# atx4vc.net
KiCad netlist of a schematic drawn in EAGLE
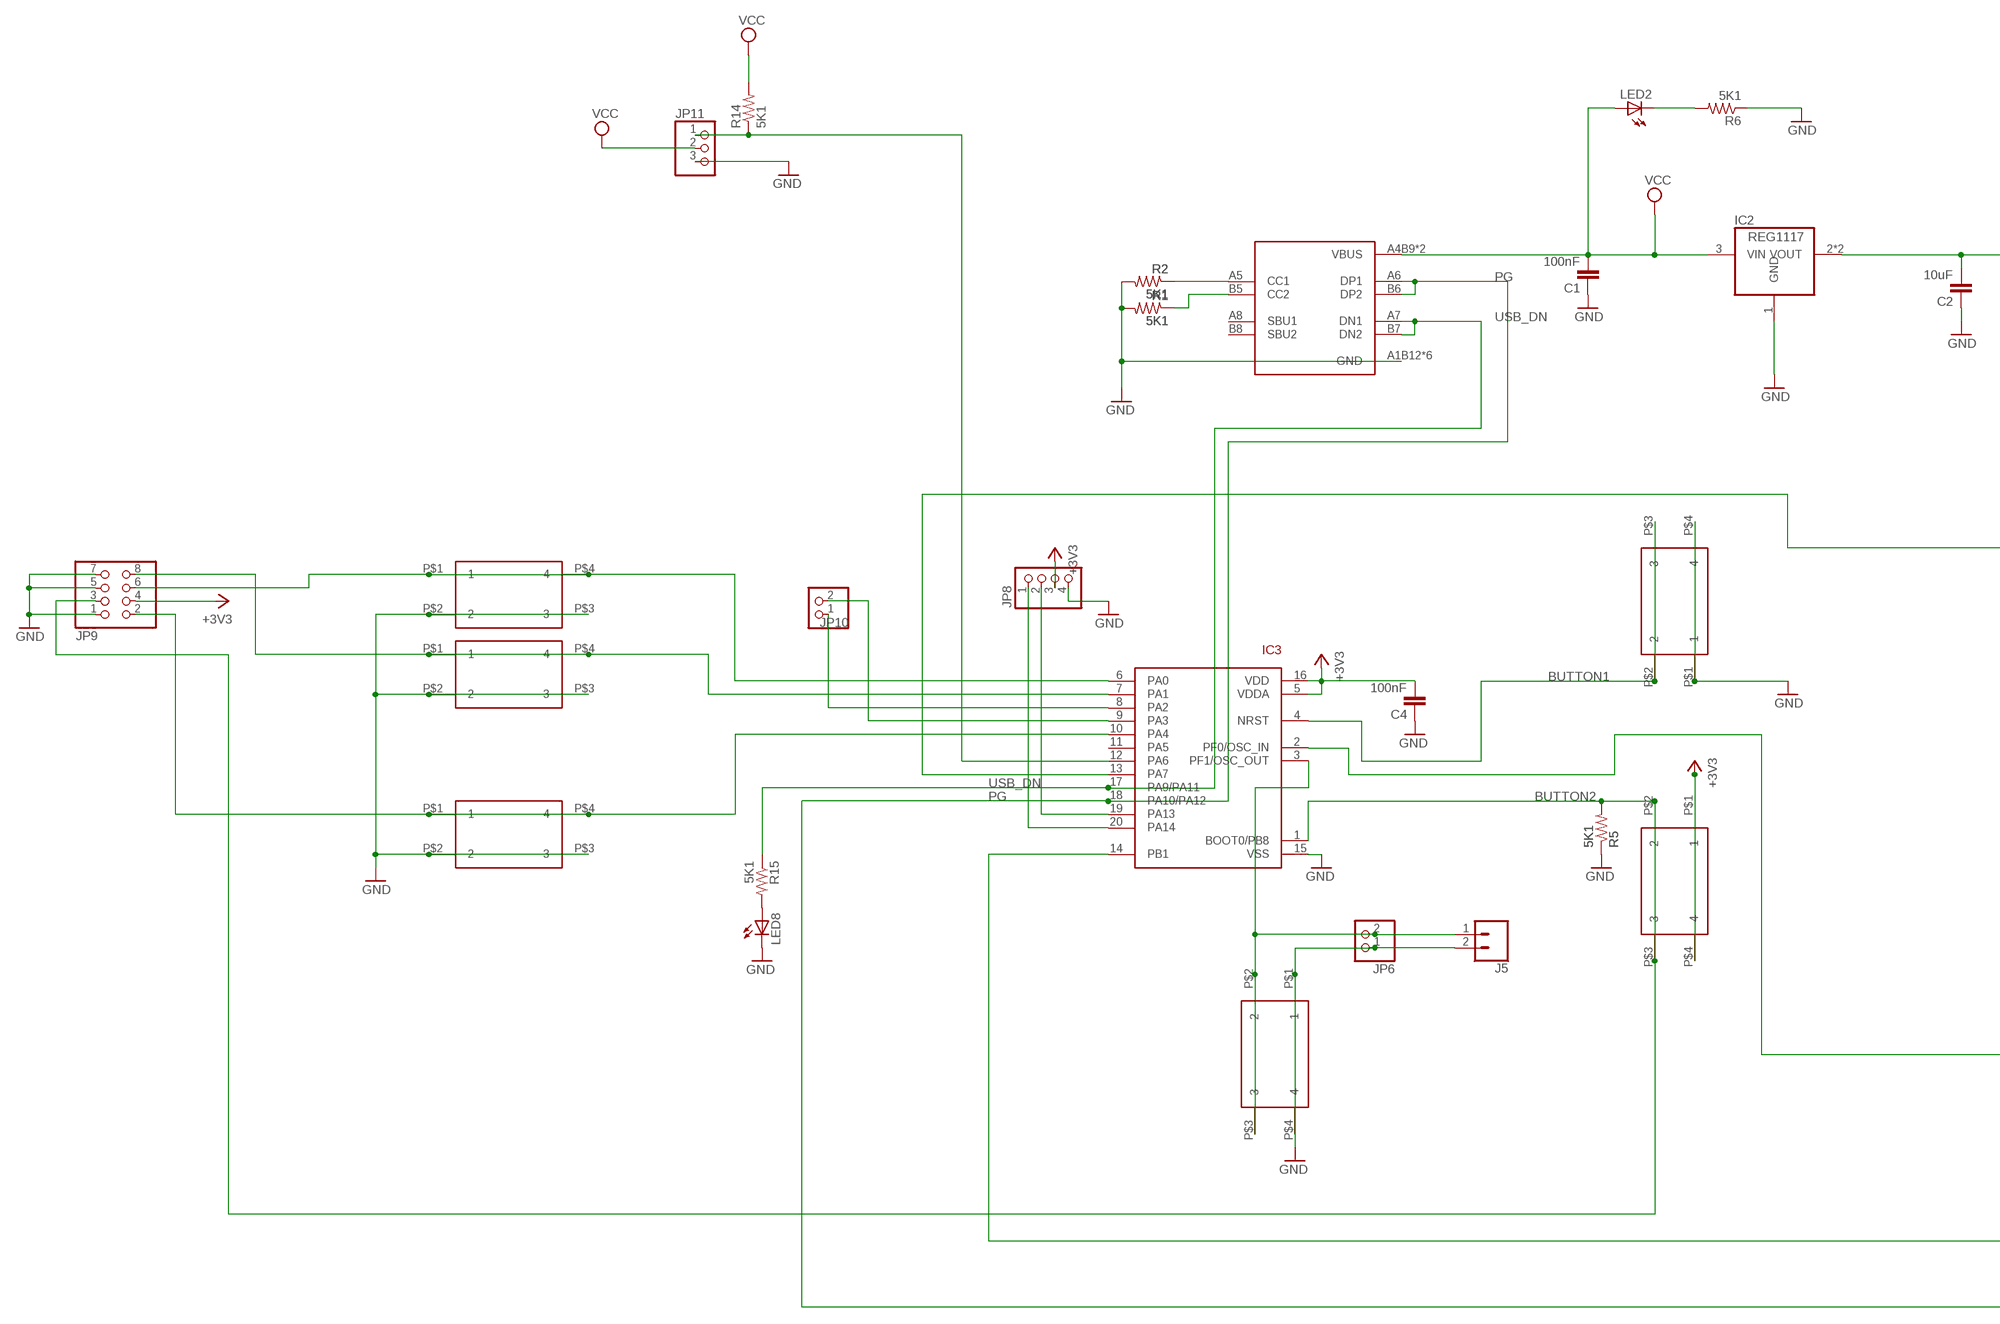
[diagram p0: schematic, sheet 1, part 1 of 2]
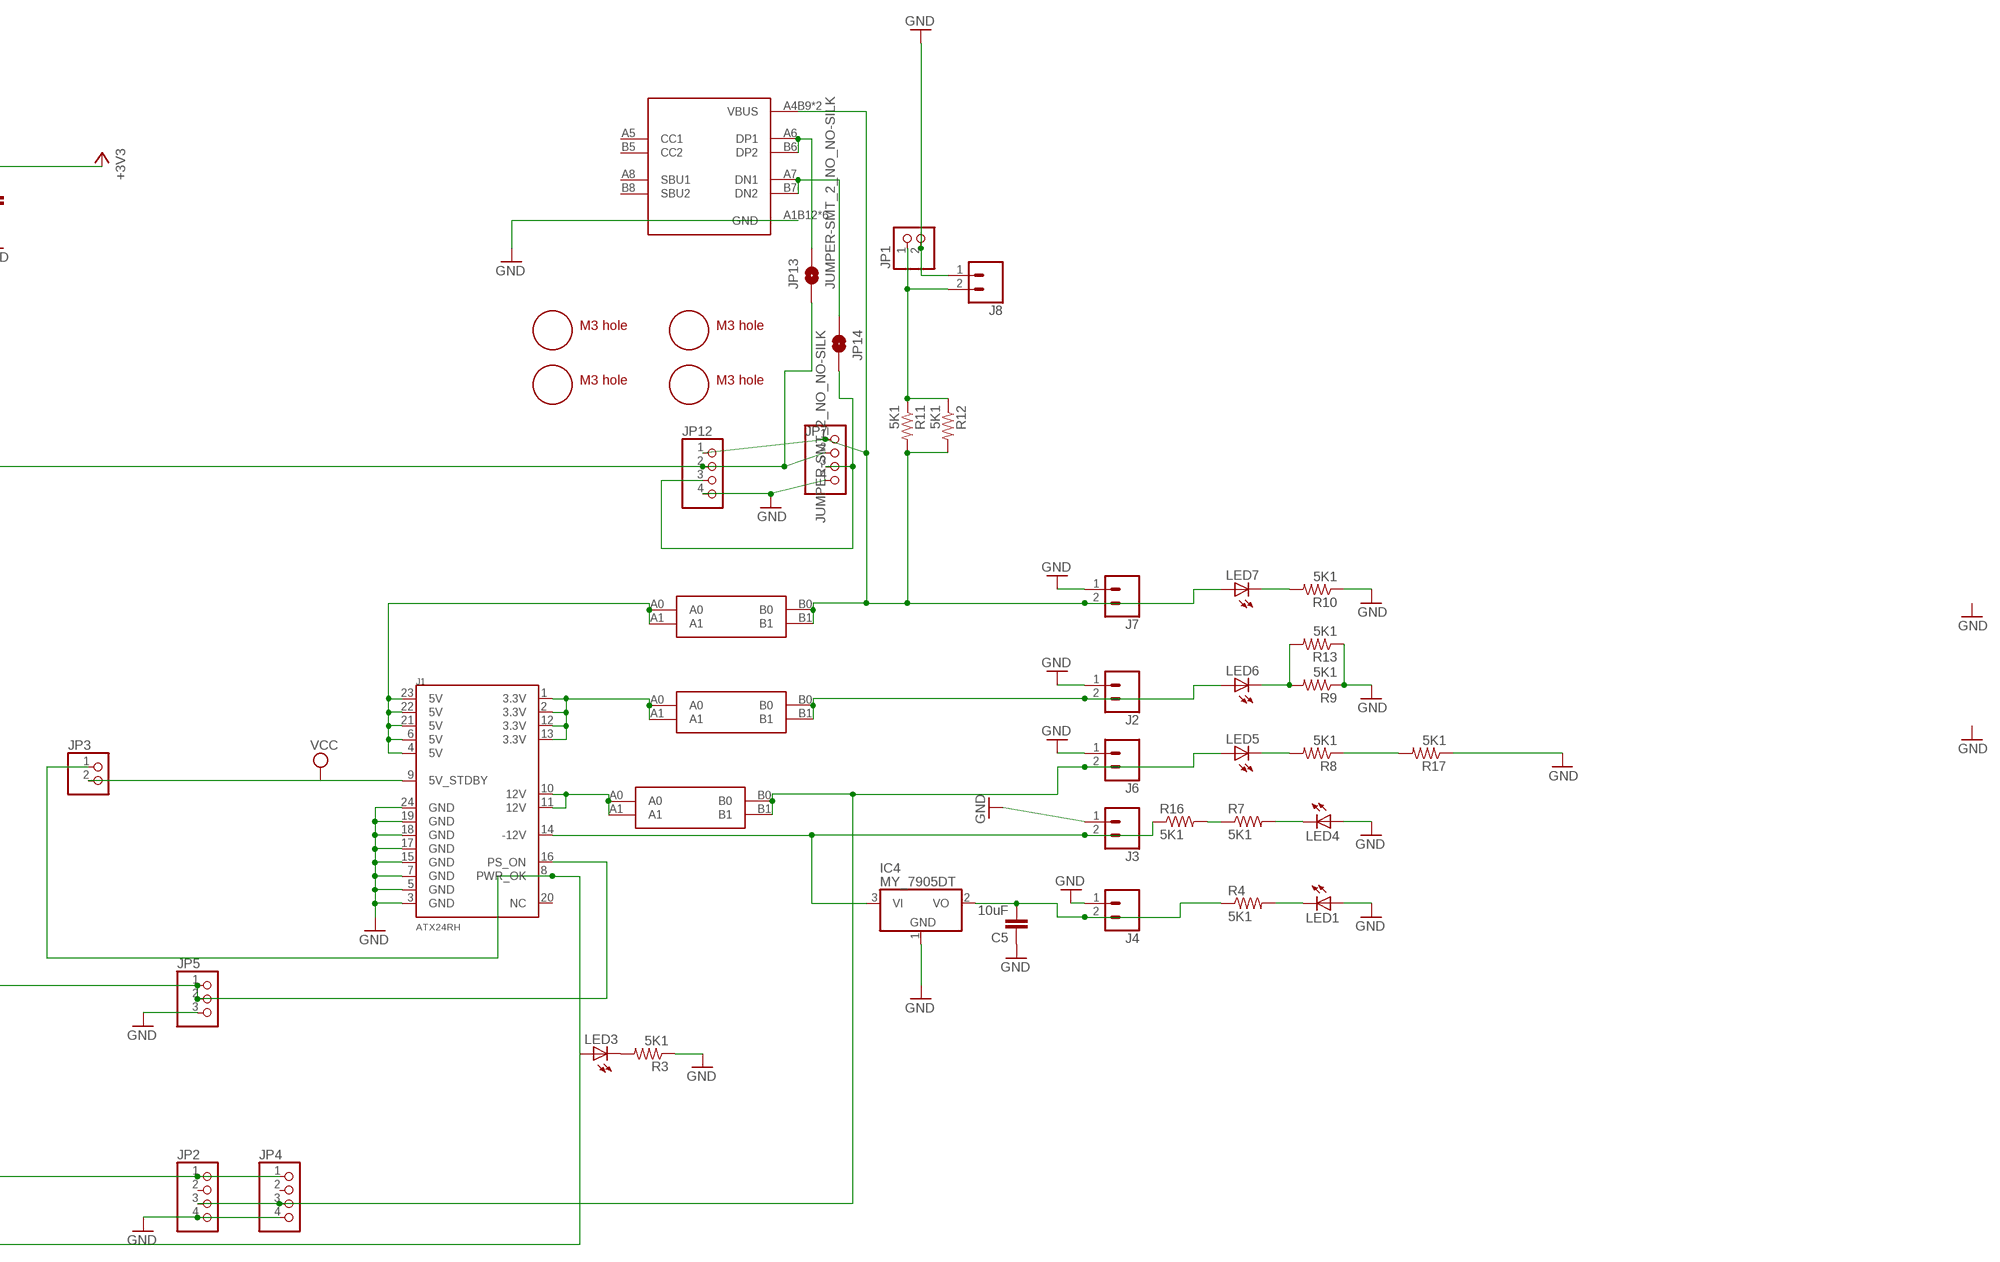
[diagram p1: schematic, sheet 1, part 2 of 2]

(export (version "E")
  (design (tool "Eeschema 10.0.6"))
  (components
    (comp (ref "C1")
      (value "100nF")
      (footprint "eagle-import:0805$1")
      (libsource (lib "eagle-import") (part "CAP0805"))
    )
    (comp (ref "C2")
      (value "10uF")
      (footprint "eagle-import:0805$1")
      (libsource (lib "eagle-import") (part "CAP0805"))
    )
    (comp (ref "C4")
      (value "100nF")
      (footprint "eagle-import:0805$1")
      (libsource (lib "eagle-import") (part "CAP0805"))
    )
    (comp (ref "C5")
      (value "10uF")
      (footprint "eagle-import:0805$1")
      (libsource (lib "eagle-import") (part "CAP0805"))
    )
    (comp (ref "IC2")
      (value "REG1117")
      (footprint "eagle-import:SOT223")
      (fields (field (name "MF") "TEXAS INSTRUMENTS") (field (name "MPN") "REG1117FAKTTT"))
      (libsource (lib "eagle-import") (part "REG1117"))
    )
    (comp (ref "IC3")
      (value "STM32F042F4")
      (footprint "eagle-import:TSSOP20")
      (libsource (lib "eagle-import") (part "STM32F042F4"))
    )
    (comp (ref "IC4")
      (value "MY_7905DT")
      (footprint "eagle-import:ADAFRUIT_TO252")
      (libsource (lib "eagle-import") (part "MY_7905DT"))
    )
    (comp (ref "J1")
      (value "ATX24RH")
      (footprint "eagle-import:ATX24_RIGHT_ANGLE")
      (libsource (lib "eagle-import") (part "ATX24RH"))
    )
    (comp (ref "J2")
      (value "CONN_023.5MM")
      (footprint "eagle-import:SCREWTERMINAL-3.5MM-2")
      (libsource (lib "eagle-import") (part "CONN_023.5MM"))
    )
    (comp (ref "J3")
      (value "CONN_023.5MM")
      (footprint "eagle-import:SCREWTERMINAL-3.5MM-2")
      (libsource (lib "eagle-import") (part "CONN_023.5MM"))
    )
    (comp (ref "J4")
      (value "CONN_023.5MM")
      (footprint "eagle-import:SCREWTERMINAL-3.5MM-2")
      (libsource (lib "eagle-import") (part "CONN_023.5MM"))
    )
    (comp (ref "J5")
      (value "CONN_023.5MM")
      (footprint "eagle-import:SCREWTERMINAL-3.5MM-2")
      (libsource (lib "eagle-import") (part "CONN_023.5MM"))
    )
    (comp (ref "J6")
      (value "CONN_023.5MM")
      (footprint "eagle-import:SCREWTERMINAL-3.5MM-2")
      (libsource (lib "eagle-import") (part "CONN_023.5MM"))
    )
    (comp (ref "J7")
      (value "CONN_023.5MM-NO_SILK")
      (footprint "eagle-import:SCREWTERMINAL-3.5MM-2-NS")
      (libsource (lib "eagle-import") (part "CONN_023.5MM-NO_SILK"))
    )
    (comp (ref "J8")
      (value "CONN_023.5MM")
      (footprint "eagle-import:SCREWTERMINAL-3.5MM-2")
      (libsource (lib "eagle-import") (part "CONN_023.5MM"))
    )
    (comp (ref "JP1")
      (value "PINHD-1X2")
      (footprint "eagle-import:1X02")
      (libsource (lib "eagle-import") (part "pinhead_325_PINHD-1X2"))
    )
    (comp (ref "JP2")
      (value "PINHD-1X4")
      (footprint "eagle-import:1X04")
      (libsource (lib "eagle-import") (part "PINHD-1X4"))
    )
    (comp (ref "JP3")
      (value "PINHD-1X2")
      (footprint "eagle-import:1X02")
      (libsource (lib "eagle-import") (part "pinhead_325_PINHD-1X2"))
    )
    (comp (ref "JP4")
      (value "PINHD-1X4")
      (footprint "eagle-import:1X04")
      (libsource (lib "eagle-import") (part "PINHD-1X4"))
    )
    (comp (ref "JP5")
      (value "PINHD-1X3:1")
      (footprint "eagle-import:1X03")
      (libsource (lib "eagle-import") (part "PINHD-1X3?{colon}1"))
    )
    (comp (ref "JP6")
      (value "PINHD-1X2")
      (footprint "eagle-import:1X02")
      (libsource (lib "eagle-import") (part "PINHD-1X2"))
    )
    (comp (ref "JP7")
      (value "PINHD-1X6")
      (footprint "eagle-import:1X06")
      (libsource (lib "eagle-import") (part "PINHD-1X6"))
    )
    (comp (ref "JP8")
      (value "PINHD-1X4")
      (footprint "eagle-import:1X04")
      (libsource (lib "eagle-import") (part "PINHD-1X4"))
    )
    (comp (ref "JP9")
      (value "PINHD-2X4")
      (footprint "eagle-import:2X04")
      (libsource (lib "eagle-import") (part "PINHD-2X4"))
    )
    (comp (ref "JP10")
      (value "PINHD-1X2")
      (footprint "eagle-import:1X02")
      (libsource (lib "eagle-import") (part "pinhead_325_PINHD-1X2"))
    )
    (comp (ref "JP11")
      (value "PINHD-1X3CB")
      (footprint "eagle-import:1X03-CLEANBIG")
      (libsource (lib "eagle-import") (part "PINHD-1X3CB"))
    )
    (comp (ref "JP12")
      (value "PINHD-1X6")
      (footprint "eagle-import:1X06")
      (libsource (lib "eagle-import") (part "PINHD-1X6"))
    )
    (comp (ref "JP13")
      (value "JUMPER-SMT_2_NO_NO-SILK")
      (footprint "eagle-import:SMT-JUMPER_2_NO_NO-SILK")
      (libsource (lib "eagle-import") (part "JUMPER-SMT_2_NO_NO-SILK"))
    )
    (comp (ref "JP14")
      (value "JUMPER-SMT_2_NO_NO-SILK")
      (footprint "eagle-import:SMT-JUMPER_2_NO_NO-SILK")
      (libsource (lib "eagle-import") (part "JUMPER-SMT_2_NO_NO-SILK"))
    )
    (comp (ref "LED1")
      (value "LEDCHIP-LED0805")
      (footprint "eagle-import:CHIP-LED0805")
      (libsource (lib "eagle-import") (part "LEDCHIP-LED0805"))
    )
    (comp (ref "LED2")
      (value "LEDCHIP-LED0805")
      (footprint "eagle-import:CHIP-LED0805")
      (libsource (lib "eagle-import") (part "LEDCHIP-LED0805"))
    )
    (comp (ref "LED3")
      (value "LEDCHIP-LED0805")
      (footprint "eagle-import:CHIP-LED0805")
      (libsource (lib "eagle-import") (part "LEDCHIP-LED0805"))
    )
    (comp (ref "LED4")
      (value "LEDCHIP-LED0805")
      (footprint "eagle-import:CHIP-LED0805")
      (libsource (lib "eagle-import") (part "LEDCHIP-LED0805"))
    )
    (comp (ref "LED5")
      (value "LEDCHIP-LED0805")
      (footprint "eagle-import:CHIP-LED0805")
      (libsource (lib "eagle-import") (part "LEDCHIP-LED0805"))
    )
    (comp (ref "LED6")
      (value "LEDCHIP-LED0805")
      (footprint "eagle-import:CHIP-LED0805")
      (libsource (lib "eagle-import") (part "LEDCHIP-LED0805"))
    )
    (comp (ref "LED7")
      (value "LEDCHIP-LED0805")
      (footprint "eagle-import:CHIP-LED0805")
      (libsource (lib "eagle-import") (part "LEDCHIP-LED0805"))
    )
    (comp (ref "LED8")
      (value "LEDCHIP-LED0805")
      (footprint "eagle-import:CHIP-LED0805")
      (libsource (lib "eagle-import") (part "LEDCHIP-LED0805"))
    )
    (comp (ref "R1")
      (value "5K1")
      (footprint "eagle-import:0805")
      (libsource (lib "eagle-import") (part "atx_power_control_RESISTOR0805-RES"))
    )
    (comp (ref "R2")
      (value "5K1")
      (footprint "eagle-import:0805")
      (libsource (lib "eagle-import") (part "atx_power_control_RESISTOR0805-RES"))
    )
    (comp (ref "R3")
      (value "5K1")
      (footprint "eagle-import:0805")
      (libsource (lib "eagle-import") (part "atx_power_control_RESISTOR0805-RES"))
    )
    (comp (ref "R4")
      (value "5K1")
      (footprint "eagle-import:0805")
      (libsource (lib "eagle-import") (part "RESISTOR0805-RES"))
    )
    (comp (ref "R5")
      (value "5K1")
      (footprint "eagle-import:0805")
      (libsource (lib "eagle-import") (part "atx_power_control_RESISTOR0805-RES"))
    )
    (comp (ref "R6")
      (value "5K1")
      (footprint "eagle-import:0805")
      (libsource (lib "eagle-import") (part "atx_power_control_RESISTOR0805-RES"))
    )
    (comp (ref "R7")
      (value "5K1")
      (footprint "eagle-import:0805")
      (libsource (lib "eagle-import") (part "RESISTOR0805-RES"))
    )
    (comp (ref "R8")
      (value "5K1")
      (footprint "eagle-import:0805")
      (libsource (lib "eagle-import") (part "atx_power_control_RESISTOR0805-RES"))
    )
    (comp (ref "R9")
      (value "5K1")
      (footprint "eagle-import:0805")
      (libsource (lib "eagle-import") (part "atx_power_control_RESISTOR0805-RES"))
    )
    (comp (ref "R10")
      (value "5K1")
      (footprint "eagle-import:0805")
      (libsource (lib "eagle-import") (part "atx_power_control_RESISTOR0805-RES"))
    )
    (comp (ref "R11")
      (value "5K1")
      (footprint "eagle-import:0805")
      (libsource (lib "eagle-import") (part "atx_power_control_RESISTOR0805-RES"))
    )
    (comp (ref "R12")
      (value "5K1")
      (footprint "eagle-import:0805")
      (libsource (lib "eagle-import") (part "atx_power_control_RESISTOR0805-RES"))
    )
    (comp (ref "R13")
      (value "5K1")
      (footprint "eagle-import:0805")
      (libsource (lib "eagle-import") (part "atx_power_control_RESISTOR0805-RES"))
    )
    (comp (ref "R14")
      (value "5K1")
      (footprint "eagle-import:0805")
      (libsource (lib "eagle-import") (part "atx_power_control_RESISTOR0805-RES"))
    )
    (comp (ref "R15")
      (value "5K1")
      (footprint "eagle-import:0805")
      (libsource (lib "eagle-import") (part "atx_power_control_RESISTOR0805-RES"))
    )
    (comp (ref "R16")
      (value "5K1")
      (footprint "eagle-import:0805")
      (libsource (lib "eagle-import") (part "RESISTOR0805-RES"))
    )
    (comp (ref "R17")
      (value "5K1")
      (footprint "eagle-import:0805")
      (libsource (lib "eagle-import") (part "atx_power_control_RESISTOR0805-RES"))
    )
    (comp (ref "SW1")
      (value "324_SW")
      (footprint "eagle-import:342_SWICH_FOOT")
      (libsource (lib "eagle-import") (part "324_SW"))
    )
    (comp (ref "SW2")
      (value "324_SW")
      (footprint "eagle-import:342_SWICH_FOOT")
      (libsource (lib "eagle-import") (part "324_SW"))
    )
    (comp (ref "SW3")
      (value "324_SW")
      (footprint "eagle-import:342_SWICH_FOOT")
      (libsource (lib "eagle-import") (part "324_SW"))
    )
    (comp (ref "SW4")
      (value "324_SW")
      (footprint "eagle-import:342_SWICH_FOOT")
      (libsource (lib "eagle-import") (part "324_SW"))
    )
    (comp (ref "SW5")
      (value "324_SW")
      (footprint "eagle-import:342_SWICH_FOOT")
      (libsource (lib "eagle-import") (part "324_SW"))
    )
    (comp (ref "SW7")
      (value "324_SW")
      (footprint "eagle-import:342_SWICH_FOOT")
      (libsource (lib "eagle-import") (part "324_SW"))
    )
    (comp (ref "U$1")
      (value "M3_MOUNTING_HOLE")
      (footprint "eagle-import:M3_MOUNTING_HOLE_PACK")
      (libsource (lib "eagle-import") (part "M3_MOUNTING_HOLE"))
    )
    (comp (ref "U$2")
      (value "M3_MOUNTING_HOLE")
      (footprint "eagle-import:M3_MOUNTING_HOLE_PACK")
      (libsource (lib "eagle-import") (part "M3_MOUNTING_HOLE"))
    )
    (comp (ref "U$3")
      (value "M3_MOUNTING_HOLE")
      (footprint "eagle-import:M3_MOUNTING_HOLE_PACK")
      (libsource (lib "eagle-import") (part "M3_MOUNTING_HOLE"))
    )
    (comp (ref "U$5")
      (value "CAR_FUSE_HOLDER3IN1")
      (footprint "eagle-import:FUSE_HOLDER_3IN1")
      (libsource (lib "eagle-import") (part "CAR_FUSE_HOLDER3IN1"))
    )
    (comp (ref "U$7")
      (value "CAR_FUSE_HOLDER3IN1")
      (footprint "eagle-import:FUSE_HOLDER_3IN1")
      (libsource (lib "eagle-import") (part "CAR_FUSE_HOLDER3IN1"))
    )
    (comp (ref "U$8")
      (value "CAR_FUSE_HOLDER3IN1")
      (footprint "eagle-import:FUSE_HOLDER_3IN1")
      (libsource (lib "eagle-import") (part "CAR_FUSE_HOLDER3IN1"))
    )
    (comp (ref "U$10")
      (value "M3_MOUNTING_HOLE")
      (footprint "eagle-import:M3_MOUNTING_HOLE_PACK")
      (libsource (lib "eagle-import") (part "M3_MOUNTING_HOLE"))
    )
    (comp (ref "U1")
      (value "USBC_16P")
      (footprint "eagle-import:USBC_16P_FOOT")
      (libsource (lib "eagle-import") (part "USBC_16P"))
    )
    (comp (ref "U2")
      (value "USBC_16P")
      (footprint "eagle-import:USBC_16P_FOOT")
      (libsource (lib "eagle-import") (part "USBC_16P"))
    )
  )
  (nets
    (net (code "1") (name "+3V3") (class "Default")
      (node (ref "C2") (pin "2") (pinfunction "2_2") (pintype "passive"))
      (node (ref "C4") (pin "2") (pinfunction "2_2") (pintype "passive"))
      (node (ref "IC2") (pin "2") (pinfunction "VOUT_2") (pintype "output"))
      (node (ref "IC2") (pin "4") (pinfunction "VOUT_4") (pintype "output"))
      (node (ref "IC3") (pin "16") (pinfunction "VDD_16") (pintype "bidirectional"))
      (node (ref "IC3") (pin "5") (pinfunction "VDDA_5") (pintype "bidirectional"))
      (node (ref "JP8") (pin "3") (pinfunction "3_3") (pintype "passive"))
      (node (ref "JP9") (pin "4") (pinfunction "4_4") (pintype "passive"))
      (node (ref "SW4") (pin "P$1") (pinfunction "1_P$1") (pintype "bidirectional"))
      (node (ref "SW4") (pin "P$4") (pinfunction "4_P$4") (pintype "bidirectional"))
    )
    (net (code "2") (name "/BUTTON1") (class "Default")
      (node (ref "IC3") (pin "4") (pinfunction "NRST_4") (pintype "bidirectional"))
      (node (ref "SW3") (pin "P$2") (pinfunction "2_P$2") (pintype "bidirectional"))
      (node (ref "SW3") (pin "P$3") (pinfunction "3_P$3") (pintype "bidirectional"))
    )
    (net (code "3") (name "/BUTTON2") (class "Default")
      (node (ref "IC3") (pin "1") (pinfunction "BOOT0/PB8_1") (pintype "bidirectional"))
      (node (ref "JP9") (pin "3") (pinfunction "3_3") (pintype "passive"))
      (node (ref "R5") (pin "2") (pinfunction "2_2") (pintype "passive"))
      (node (ref "SW4") (pin "P$2") (pinfunction "2_P$2") (pintype "bidirectional"))
      (node (ref "SW4") (pin "P$3") (pinfunction "3_P$3") (pintype "bidirectional"))
    )
    (net (code "4") (name "/PG") (class "Default")
      (node (ref "IC3") (pin "18") (pinfunction "PA10/PA12_18") (pintype "bidirectional"))
      (node (ref "J1") (pin "8") (pinfunction "PWR_OK_8") (pintype "bidirectional"))
      (node (ref "JP3") (pin "1") (pinfunction "1_1") (pintype "passive"))
      (node (ref "LED3") (pin "A") (pinfunction "A_A") (pintype "passive"))
      (node (ref "U2") (pin "A6") (pinfunction "DP1_A6") (pintype "bidirectional"))
      (node (ref "U2") (pin "B6") (pinfunction "DP2_B6") (pintype "bidirectional"))
    )
    (net (code "5") (name "/USB_DN") (class "Default")
      (node (ref "IC3") (pin "17") (pinfunction "PA9/PA11_17") (pintype "bidirectional"))
      (node (ref "R15") (pin "1") (pinfunction "1_1") (pintype "passive"))
      (node (ref "U2") (pin "A7") (pinfunction "DN1_A7") (pintype "bidirectional"))
      (node (ref "U2") (pin "B7") (pinfunction "DN2_B7") (pintype "bidirectional"))
    )
    (net (code "6") (name "GND") (class "Default")
      (node (ref "C1") (pin "1") (pinfunction "1_1") (pintype "passive"))
      (node (ref "C2") (pin "1") (pinfunction "1_1") (pintype "passive"))
      (node (ref "C4") (pin "1") (pinfunction "1_1") (pintype "passive"))
      (node (ref "C5") (pin "1") (pinfunction "1_1") (pintype "passive"))
      (node (ref "IC2") (pin "1") (pinfunction "GND_1") (pintype "power_in"))
      (node (ref "IC3") (pin "15") (pinfunction "VSS_15") (pintype "bidirectional"))
      (node (ref "IC4") (pin "1") (pinfunction "GND_1") (pintype "passive"))
      (node (ref "J1") (pin "15") (pinfunction "GND_15") (pintype "bidirectional"))
      (node (ref "J1") (pin "17") (pinfunction "GND_17") (pintype "bidirectional"))
      (node (ref "J1") (pin "18") (pinfunction "GND_18") (pintype "bidirectional"))
      (node (ref "J1") (pin "19") (pinfunction "GND_19") (pintype "bidirectional"))
      (node (ref "J1") (pin "24") (pinfunction "GND_24") (pintype "bidirectional"))
      (node (ref "J1") (pin "3") (pinfunction "GND_3") (pintype "bidirectional"))
      (node (ref "J1") (pin "5") (pinfunction "GND_5") (pintype "bidirectional"))
      (node (ref "J1") (pin "7") (pinfunction "GND_7") (pintype "bidirectional"))
      (node (ref "J2") (pin "1") (pinfunction "1_1") (pintype "passive"))
      (node (ref "J3") (pin "1") (pinfunction "1_1") (pintype "passive"))
      (node (ref "J4") (pin "1") (pinfunction "1_1") (pintype "passive"))
      (node (ref "J5") (pin "2") (pinfunction "2_2") (pintype "passive"))
      (node (ref "J6") (pin "1") (pinfunction "1_1") (pintype "passive"))
      (node (ref "J7") (pin "1") (pinfunction "1_1") (pintype "passive"))
      (node (ref "J8") (pin "1") (pinfunction "1_1") (pintype "passive"))
      (node (ref "JP1") (pin "2") (pinfunction "2_2") (pintype "passive"))
      (node (ref "JP11") (pin "3") (pinfunction "3_3") (pintype "passive"))
      (node (ref "JP12") (pin "4") (pinfunction "4_4") (pintype "passive"))
      (node (ref "JP2") (pin "4") (pinfunction "4_4") (pintype "passive"))
      (node (ref "JP4") (pin "4") (pinfunction "4_4") (pintype "passive"))
      (node (ref "JP5") (pin "3") (pinfunction "3_3") (pintype "passive"))
      (node (ref "JP6") (pin "1") (pinfunction "1_1") (pintype "passive"))
      (node (ref "JP7") (pin "4") (pinfunction "4_4") (pintype "passive"))
      (node (ref "JP8") (pin "4") (pinfunction "4_4") (pintype "passive"))
      (node (ref "JP9") (pin "1") (pinfunction "1_1") (pintype "passive"))
      (node (ref "JP9") (pin "5") (pinfunction "5_5") (pintype "passive"))
      (node (ref "JP9") (pin "7") (pinfunction "7_7") (pintype "passive"))
      (node (ref "LED1") (pin "A") (pinfunction "A_A") (pintype "passive"))
      (node (ref "LED4") (pin "A") (pinfunction "A_A") (pintype "passive"))
      (node (ref "LED8") (pin "C") (pinfunction "C_C") (pintype "passive"))
      (node (ref "R1") (pin "2") (pinfunction "2_2") (pintype "passive"))
      (node (ref "R10") (pin "1") (pinfunction "1_1") (pintype "passive"))
      (node (ref "R13") (pin "1") (pinfunction "1_1") (pintype "passive"))
      (node (ref "R17") (pin "1") (pinfunction "1_1") (pintype "passive"))
      (node (ref "R2") (pin "2") (pinfunction "2_2") (pintype "passive"))
      (node (ref "R3") (pin "1") (pinfunction "1_1") (pintype "passive"))
      (node (ref "R5") (pin "1") (pinfunction "1_1") (pintype "passive"))
      (node (ref "R6") (pin "1") (pinfunction "1_1") (pintype "passive"))
      (node (ref "R9") (pin "1") (pinfunction "1_1") (pintype "passive"))
      (node (ref "SW1") (pin "P$1") (pinfunction "1_P$1") (pintype "bidirectional"))
      (node (ref "SW1") (pin "P$4") (pinfunction "4_P$4") (pintype "bidirectional"))
      (node (ref "SW2") (pin "P$2") (pinfunction "2_P$2") (pintype "bidirectional"))
      (node (ref "SW2") (pin "P$3") (pinfunction "3_P$3") (pintype "bidirectional"))
      (node (ref "SW3") (pin "P$1") (pinfunction "1_P$1") (pintype "bidirectional"))
      (node (ref "SW3") (pin "P$4") (pinfunction "4_P$4") (pintype "bidirectional"))
      (node (ref "SW5") (pin "P$2") (pinfunction "2_P$2") (pintype "bidirectional"))
      (node (ref "SW5") (pin "P$3") (pinfunction "3_P$3") (pintype "bidirectional"))
      (node (ref "SW7") (pin "P$2") (pinfunction "2_P$2") (pintype "bidirectional"))
      (node (ref "SW7") (pin "P$3") (pinfunction "3_P$3") (pintype "bidirectional"))
      (node (ref "U1") (pin "A1B12") (pinfunction "GND_A1B12") (pintype "bidirectional"))
      (node (ref "U1") (pin "B11A12") (pinfunction "GND_B11A12") (pintype "bidirectional"))
      (node (ref "U1") (pin "P$13") (pinfunction "GND_P$13") (pintype "bidirectional"))
      (node (ref "U1") (pin "P$14") (pinfunction "GND_P$14") (pintype "bidirectional"))
      (node (ref "U1") (pin "P$15") (pinfunction "GND_P$15") (pintype "bidirectional"))
      (node (ref "U1") (pin "P$16") (pinfunction "GND_P$16") (pintype "bidirectional"))
      (node (ref "U2") (pin "A1B12") (pinfunction "GND_A1B12") (pintype "bidirectional"))
      (node (ref "U2") (pin "B11A12") (pinfunction "GND_B11A12") (pintype "bidirectional"))
      (node (ref "U2") (pin "P$13") (pinfunction "GND_P$13") (pintype "bidirectional"))
      (node (ref "U2") (pin "P$14") (pinfunction "GND_P$14") (pintype "bidirectional"))
      (node (ref "U2") (pin "P$15") (pinfunction "GND_P$15") (pintype "bidirectional"))
      (node (ref "U2") (pin "P$16") (pinfunction "GND_P$16") (pintype "bidirectional"))
    )
    (net (code "7") (name "Net-(IC3-PA0)") (class "Default")
      (node (ref "IC3") (pin "6") (pinfunction "PA0_6") (pintype "bidirectional"))
      (node (ref "JP9") (pin "6") (pinfunction "6_6") (pintype "passive"))
      (node (ref "SW2") (pin "P$1") (pinfunction "1_P$1") (pintype "bidirectional"))
      (node (ref "SW2") (pin "P$4") (pinfunction "4_P$4") (pintype "bidirectional"))
    )
    (net (code "8") (name "Net-(IC3-PA1)") (class "Default")
      (node (ref "IC3") (pin "7") (pinfunction "PA1_7") (pintype "bidirectional"))
      (node (ref "JP9") (pin "8") (pinfunction "8_8") (pintype "passive"))
      (node (ref "SW5") (pin "P$1") (pinfunction "1_P$1") (pintype "bidirectional"))
      (node (ref "SW5") (pin "P$4") (pinfunction "4_P$4") (pintype "bidirectional"))
    )
    (net (code "9") (name "Net-(IC3-PA2)") (class "Default")
      (node (ref "IC3") (pin "8") (pinfunction "PA2_8") (pintype "bidirectional"))
      (node (ref "JP10") (pin "1") (pinfunction "1_1") (pintype "passive"))
    )
    (net (code "10") (name "Net-(IC3-PA3)") (class "Default")
      (node (ref "IC3") (pin "9") (pinfunction "PA3_9") (pintype "bidirectional"))
      (node (ref "JP10") (pin "2") (pinfunction "2_2") (pintype "passive"))
    )
    (net (code "11") (name "Net-(IC3-PA4)") (class "Default")
      (node (ref "IC3") (pin "10") (pinfunction "PA4_10") (pintype "bidirectional"))
      (node (ref "JP9") (pin "2") (pinfunction "2_2") (pintype "passive"))
      (node (ref "SW7") (pin "P$1") (pinfunction "1_P$1") (pintype "bidirectional"))
      (node (ref "SW7") (pin "P$4") (pinfunction "4_P$4") (pintype "bidirectional"))
    )
    (net (code "12") (name "Net-(IC3-PA6)") (class "Default")
      (node (ref "IC3") (pin "12") (pinfunction "PA6_12") (pintype "bidirectional"))
      (node (ref "JP11") (pin "1") (pinfunction "1_1") (pintype "passive"))
      (node (ref "R14") (pin "1") (pinfunction "1_1") (pintype "passive"))
    )
    (net (code "13") (name "Net-(IC3-PA7)") (class "Default")
      (node (ref "IC3") (pin "13") (pinfunction "PA7_13") (pintype "bidirectional"))
      (node (ref "JP12") (pin "2") (pinfunction "2_2") (pintype "passive"))
      (node (ref "JP13") (pin "1") (pinfunction "1_1") (pintype "passive"))
      (node (ref "JP7") (pin "2") (pinfunction "2_2") (pintype "passive"))
    )
    (net (code "14") (name "Net-(IC3-PA13)") (class "Default")
      (node (ref "IC3") (pin "19") (pinfunction "PA13_19") (pintype "bidirectional"))
      (node (ref "JP8") (pin "2") (pinfunction "2_2") (pintype "passive"))
    )
    (net (code "15") (name "Net-(IC3-PA14)") (class "Default")
      (node (ref "IC3") (pin "20") (pinfunction "PA14_20") (pintype "bidirectional"))
      (node (ref "JP8") (pin "1") (pinfunction "1_1") (pintype "passive"))
    )
    (net (code "16") (name "Net-(IC3-PB1)") (class "Default")
      (node (ref "IC3") (pin "14") (pinfunction "PB1_14") (pintype "bidirectional"))
      (node (ref "JP2") (pin "1") (pinfunction "1_1") (pintype "passive"))
      (node (ref "JP4") (pin "1") (pinfunction "1_1") (pintype "passive"))
    )
    (net (code "17") (name "Net-(IC3-PF0{slash}OSC_IN)") (class "Default")
      (node (ref "IC3") (pin "2") (pinfunction "PF0/OSC_IN_2") (pintype "bidirectional"))
      (node (ref "J1") (pin "16") (pinfunction "PS_ON_16") (pintype "bidirectional"))
      (node (ref "JP5") (pin "1") (pinfunction "1_1") (pintype "passive"))
      (node (ref "JP5") (pin "2") (pinfunction "2_2") (pintype "passive"))
    )
    (net (code "18") (name "Net-(IC3-PF1{slash}OSC_OUT)") (class "Default")
      (node (ref "IC3") (pin "3") (pinfunction "PF1/OSC_OUT_3") (pintype "bidirectional"))
      (node (ref "J5") (pin "1") (pinfunction "1_1") (pintype "passive"))
      (node (ref "JP6") (pin "2") (pinfunction "2_2") (pintype "passive"))
      (node (ref "SW1") (pin "P$2") (pinfunction "2_P$2") (pintype "bidirectional"))
      (node (ref "SW1") (pin "P$3") (pinfunction "3_P$3") (pintype "bidirectional"))
    )
    (net (code "19") (name "Net-(IC4-VI)") (class "Default")
      (node (ref "IC4") (pin "3") (pinfunction "VI_3") (pintype "input"))
      (node (ref "J1") (pin "14") (pinfunction "-12V_14") (pintype "bidirectional"))
      (node (ref "J3") (pin "2") (pinfunction "2_2") (pintype "passive"))
      (node (ref "R16") (pin "1") (pinfunction "1_1") (pintype "passive"))
    )
    (net (code "20") (name "Net-(IC4-VO)") (class "Default")
      (node (ref "C5") (pin "2") (pinfunction "2_2") (pintype "passive"))
      (node (ref "IC4") (pin "2") (pinfunction "VO_2") (pintype "passive"))
      (node (ref "J4") (pin "2") (pinfunction "2_2") (pintype "passive"))
      (node (ref "R4") (pin "1") (pinfunction "1_1") (pintype "passive"))
    )
    (net (code "21") (name "Net-(J1-3.3V-Pad1)") (class "Default")
      (node (ref "J1") (pin "1") (pinfunction "3.3V_1") (pintype "bidirectional"))
      (node (ref "J1") (pin "12") (pinfunction "3.3V_12") (pintype "bidirectional"))
      (node (ref "J1") (pin "13") (pinfunction "3.3V_13") (pintype "bidirectional"))
      (node (ref "J1") (pin "2") (pinfunction "3.3V_2") (pintype "bidirectional"))
      (node (ref "U$7") (pin "A0") (pinfunction "A0_A0") (pintype "bidirectional"))
      (node (ref "U$7") (pin "A1") (pinfunction "A1_A1") (pintype "bidirectional"))
    )
    (net (code "22") (name "Net-(J1-5V-Pad21)") (class "Default")
      (node (ref "J1") (pin "21") (pinfunction "5V_21") (pintype "bidirectional"))
      (node (ref "J1") (pin "22") (pinfunction "5V_22") (pintype "bidirectional"))
      (node (ref "J1") (pin "23") (pinfunction "5V_23") (pintype "bidirectional"))
      (node (ref "J1") (pin "4") (pinfunction "5V_4") (pintype "bidirectional"))
      (node (ref "J1") (pin "6") (pinfunction "5V_6") (pintype "bidirectional"))
      (node (ref "U$8") (pin "A0") (pinfunction "A0_A0") (pintype "bidirectional"))
      (node (ref "U$8") (pin "A1") (pinfunction "A1_A1") (pintype "bidirectional"))
    )
    (net (code "23") (name "Net-(J1-12V-Pad10)") (class "Default")
      (node (ref "J1") (pin "10") (pinfunction "12V_10") (pintype "bidirectional"))
      (node (ref "J1") (pin "11") (pinfunction "12V_11") (pintype "bidirectional"))
      (node (ref "U$5") (pin "A0") (pinfunction "A0_A0") (pintype "bidirectional"))
      (node (ref "U$5") (pin "A1") (pinfunction "A1_A1") (pintype "bidirectional"))
    )
    (net (code "24") (name "Net-(J2-Pad2)") (class "Default")
      (node (ref "J2") (pin "2") (pinfunction "2_2") (pintype "passive"))
      (node (ref "LED6") (pin "A") (pinfunction "A_A") (pintype "passive"))
      (node (ref "U$7") (pin "B0") (pinfunction "B0_B0") (pintype "bidirectional"))
      (node (ref "U$7") (pin "B1") (pinfunction "B1_B1") (pintype "bidirectional"))
    )
    (net (code "25") (name "Net-(J6-Pad2)") (class "Default")
      (node (ref "J6") (pin "2") (pinfunction "2_2") (pintype "passive"))
      (node (ref "JP2") (pin "3") (pinfunction "3_3") (pintype "passive"))
      (node (ref "JP4") (pin "3") (pinfunction "3_3") (pintype "passive"))
      (node (ref "LED5") (pin "A") (pinfunction "A_A") (pintype "passive"))
      (node (ref "U$5") (pin "B0") (pinfunction "B0_B0") (pintype "bidirectional"))
      (node (ref "U$5") (pin "B1") (pinfunction "B1_B1") (pintype "bidirectional"))
    )
    (net (code "26") (name "Net-(J7-Pad2)") (class "Default")
      (node (ref "J7") (pin "2") (pinfunction "2_2") (pintype "passive"))
      (node (ref "JP12") (pin "1") (pinfunction "1_1") (pintype "passive"))
      (node (ref "JP7") (pin "1") (pinfunction "1_1") (pintype "passive"))
      (node (ref "LED7") (pin "A") (pinfunction "A_A") (pintype "passive"))
      (node (ref "R11") (pin "2") (pinfunction "2_2") (pintype "passive"))
      (node (ref "R12") (pin "2") (pinfunction "2_2") (pintype "passive"))
      (node (ref "U$8") (pin "B0") (pinfunction "B0_B0") (pintype "bidirectional"))
      (node (ref "U$8") (pin "B1") (pinfunction "B1_B1") (pintype "bidirectional"))
      (node (ref "U1") (pin "A4B9") (pinfunction "VBUS_A4B9") (pintype "bidirectional"))
      (node (ref "U1") (pin "B4A9") (pinfunction "VBUS_B4A9") (pintype "bidirectional"))
    )
    (net (code "27") (name "Net-(J8-Pad2)") (class "Default")
      (node (ref "J8") (pin "2") (pinfunction "2_2") (pintype "passive"))
      (node (ref "JP1") (pin "1") (pinfunction "1_1") (pintype "passive"))
      (node (ref "R11") (pin "1") (pinfunction "1_1") (pintype "passive"))
      (node (ref "R12") (pin "1") (pinfunction "1_1") (pintype "passive"))
    )
    (net (code "28") (name "Net-(JP12-Pad3)") (class "Default")
      (node (ref "JP12") (pin "3") (pinfunction "3_3") (pintype "passive"))
      (node (ref "JP14") (pin "2") (pinfunction "2_2") (pintype "passive"))
      (node (ref "JP7") (pin "3") (pinfunction "3_3") (pintype "passive"))
    )
    (net (code "29") (name "Net-(LED1-PadC)") (class "Default")
      (node (ref "LED1") (pin "C") (pinfunction "C_C") (pintype "passive"))
      (node (ref "R4") (pin "2") (pinfunction "2_2") (pintype "passive"))
    )
    (net (code "30") (name "Net-(LED2-PadC)") (class "Default")
      (node (ref "LED2") (pin "C") (pinfunction "C_C") (pintype "passive"))
      (node (ref "R6") (pin "2") (pinfunction "2_2") (pintype "passive"))
    )
    (net (code "31") (name "Net-(LED3-PadC)") (class "Default")
      (node (ref "LED3") (pin "C") (pinfunction "C_C") (pintype "passive"))
      (node (ref "R3") (pin "2") (pinfunction "2_2") (pintype "passive"))
    )
    (net (code "32") (name "Net-(LED4-PadC)") (class "Default")
      (node (ref "LED4") (pin "C") (pinfunction "C_C") (pintype "passive"))
      (node (ref "R7") (pin "2") (pinfunction "2_2") (pintype "passive"))
    )
    (net (code "33") (name "Net-(LED5-PadC)") (class "Default")
      (node (ref "LED5") (pin "C") (pinfunction "C_C") (pintype "passive"))
      (node (ref "R8") (pin "2") (pinfunction "2_2") (pintype "passive"))
    )
    (net (code "34") (name "Net-(LED6-PadC)") (class "Default")
      (node (ref "LED6") (pin "C") (pinfunction "C_C") (pintype "passive"))
      (node (ref "R13") (pin "2") (pinfunction "2_2") (pintype "passive"))
      (node (ref "R9") (pin "2") (pinfunction "2_2") (pintype "passive"))
    )
    (net (code "35") (name "Net-(LED7-PadC)") (class "Default")
      (node (ref "LED7") (pin "C") (pinfunction "C_C") (pintype "passive"))
      (node (ref "R10") (pin "2") (pinfunction "2_2") (pintype "passive"))
    )
    (net (code "36") (name "Net-(LED8-PadA)") (class "Default")
      (node (ref "LED8") (pin "A") (pinfunction "A_A") (pintype "passive"))
      (node (ref "R15") (pin "2") (pinfunction "2_2") (pintype "passive"))
    )
    (net (code "37") (name "Net-(R16-Pad2)") (class "Default")
      (node (ref "R16") (pin "2") (pinfunction "2_2") (pintype "passive"))
      (node (ref "R7") (pin "1") (pinfunction "1_1") (pintype "passive"))
    )
    (net (code "38") (name "Net-(R17-Pad2)") (class "Default")
      (node (ref "R17") (pin "2") (pinfunction "2_2") (pintype "passive"))
      (node (ref "R8") (pin "1") (pinfunction "1_1") (pintype "passive"))
    )
    (net (code "39") (name "Net-(U1-DN1)") (class "Default")
      (node (ref "JP14") (pin "1") (pinfunction "1_1") (pintype "passive"))
      (node (ref "U1") (pin "A7") (pinfunction "DN1_A7") (pintype "bidirectional"))
      (node (ref "U1") (pin "B7") (pinfunction "DN2_B7") (pintype "bidirectional"))
    )
    (net (code "40") (name "Net-(U1-DP1)") (class "Default")
      (node (ref "JP13") (pin "2") (pinfunction "2_2") (pintype "passive"))
      (node (ref "U1") (pin "A6") (pinfunction "DP1_A6") (pintype "bidirectional"))
      (node (ref "U1") (pin "B6") (pinfunction "DP2_B6") (pintype "bidirectional"))
    )
    (net (code "41") (name "Net-(U2-CC1)") (class "Default")
      (node (ref "R2") (pin "1") (pinfunction "1_1") (pintype "passive"))
      (node (ref "U2") (pin "A5") (pinfunction "CC1_A5") (pintype "bidirectional"))
    )
    (net (code "42") (name "Net-(U2-CC2)") (class "Default")
      (node (ref "R1") (pin "1") (pinfunction "1_1") (pintype "passive"))
      (node (ref "U2") (pin "B5") (pinfunction "CC2_B5") (pintype "bidirectional"))
    )
    (net (code "43") (name "VCC") (class "Default")
      (node (ref "C1") (pin "2") (pinfunction "2_2") (pintype "passive"))
      (node (ref "IC2") (pin "3") (pinfunction "VIN_3") (pintype "input"))
      (node (ref "J1") (pin "9") (pinfunction "5V_STDBY_9") (pintype "bidirectional"))
      (node (ref "JP11") (pin "2") (pinfunction "2_2") (pintype "passive"))
      (node (ref "JP3") (pin "2") (pinfunction "2_2") (pintype "passive"))
      (node (ref "LED2") (pin "A") (pinfunction "A_A") (pintype "passive"))
      (node (ref "R14") (pin "2") (pinfunction "2_2") (pintype "passive"))
      (node (ref "U2") (pin "A4B9") (pinfunction "VBUS_A4B9") (pintype "bidirectional"))
      (node (ref "U2") (pin "B4A9") (pinfunction "VBUS_B4A9") (pintype "bidirectional"))
    )
    (net (code "44") (name "unconnected-(IC3-PA5-Pad11)") (class "Default")
      (node (ref "IC3") (pin "11") (pinfunction "PA5_11") (pintype "bidirectional"))
    )
    (net (code "45") (name "unconnected-(J1-NC-Pad20)") (class "Default")
      (node (ref "J1") (pin "20") (pinfunction "NC_20") (pintype "bidirectional"))
    )
    (net (code "46") (name "unconnected-(JP2-Pad2)") (class "Default")
      (node (ref "JP2") (pin "2") (pinfunction "2_2") (pintype "passive"))
    )
    (net (code "47") (name "unconnected-(JP4-Pad2)") (class "Default")
      (node (ref "JP4") (pin "2") (pinfunction "2_2") (pintype "passive"))
    )
    (net (code "48") (name "unconnected-(U1-CC1-PadA5)") (class "Default")
      (node (ref "U1") (pin "A5") (pinfunction "CC1_A5") (pintype "bidirectional"))
    )
    (net (code "49") (name "unconnected-(U1-CC2-PadB5)") (class "Default")
      (node (ref "U1") (pin "B5") (pinfunction "CC2_B5") (pintype "bidirectional"))
    )
    (net (code "50") (name "unconnected-(U1-SBU1-PadA8)") (class "Default")
      (node (ref "U1") (pin "A8") (pinfunction "SBU1_A8") (pintype "bidirectional"))
    )
    (net (code "51") (name "unconnected-(U1-SBU2-PadB8)") (class "Default")
      (node (ref "U1") (pin "B8") (pinfunction "SBU2_B8") (pintype "bidirectional"))
    )
    (net (code "52") (name "unconnected-(U2-SBU1-PadA8)") (class "Default")
      (node (ref "U2") (pin "A8") (pinfunction "SBU1_A8") (pintype "bidirectional"))
    )
    (net (code "53") (name "unconnected-(U2-SBU2-PadB8)") (class "Default")
      (node (ref "U2") (pin "B8") (pinfunction "SBU2_B8") (pintype "bidirectional"))
    )
  )
)
